# EntradaSensores.net
KiCad netlist of a schematic drawn in Altium Designer
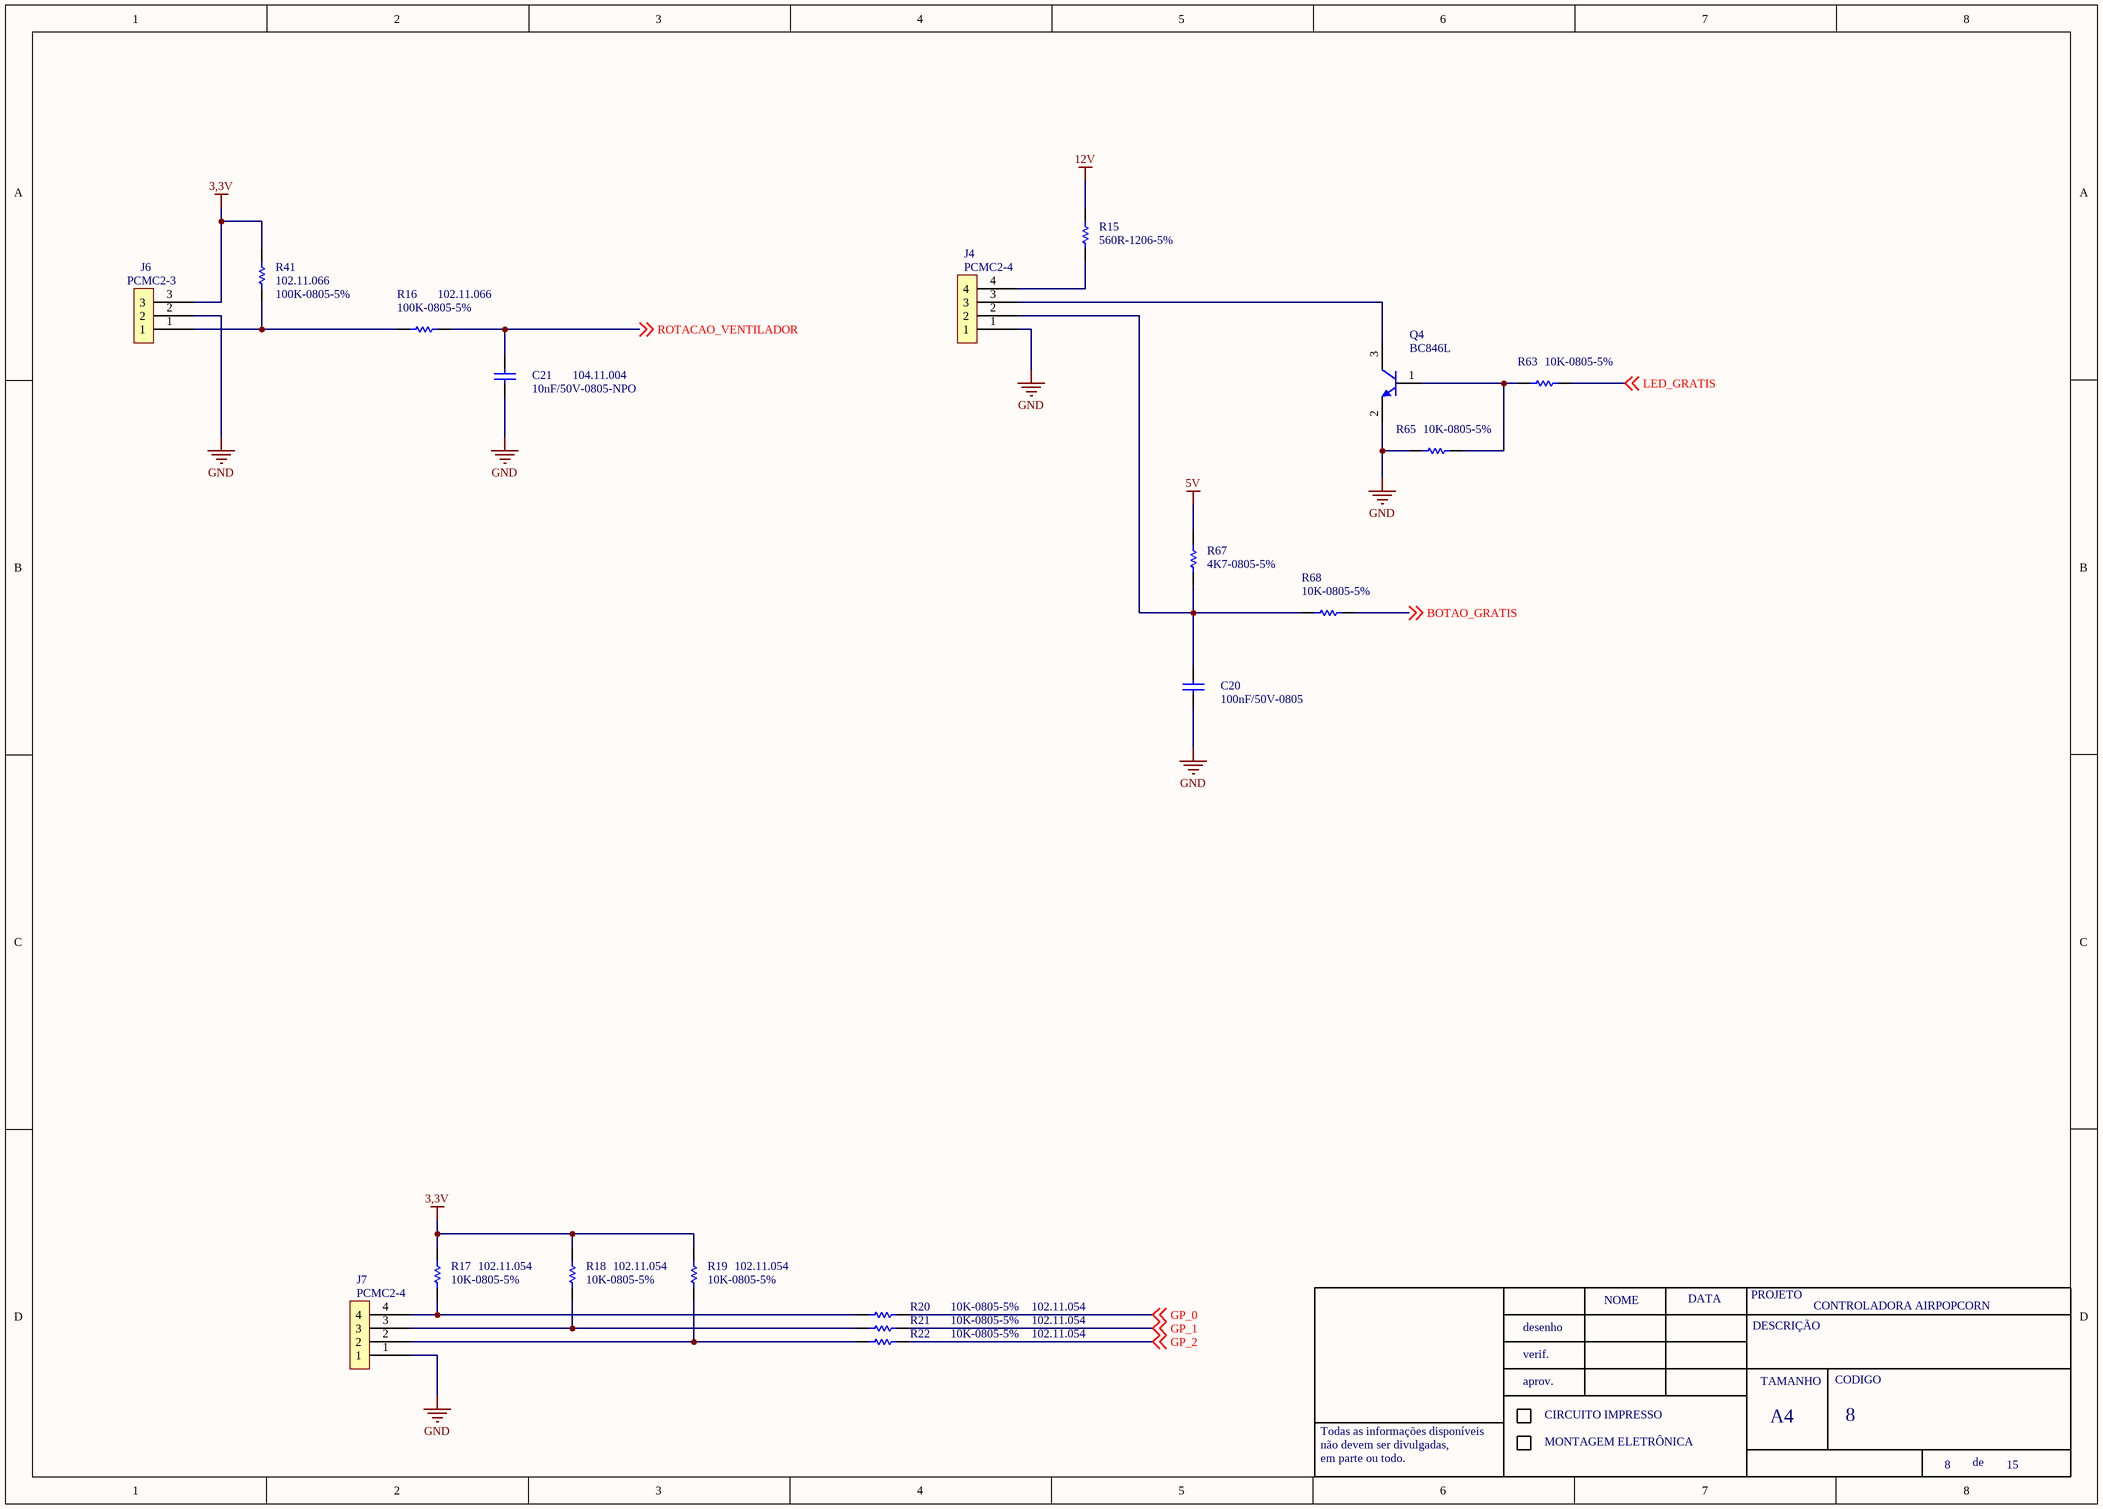
[diagram p0: EntradaSensores.SchDoc]

(export (version "E")
  (design (tool "Eeschema 10.0.6"))
  (components
    (comp (ref "C20")
      (value "100nF/50V-0805")
      (description "100nF/50-0805-NPO")
      (libsource (lib "AquinoLib") (part "100nF/50-0805-NPO"))
    )
    (comp (ref "C21")
      (value "10nF/50V-0805-NPO")
      (footprint "0805-REVISADO ONDA")
      (fields (field (name "ERP") "104.11.004"))
      (libsource (lib "AquinoLib") (part "10nF/50V-0805-NPO"))
    )
    (comp (ref "J4") (value "PCMC2-4") (footprint "PCMC2-4") (libsource (lib "AquinoLib") (part "PCMC2-4")))
    (comp (ref "J6") (value "PCMC2-3") (footprint "PCMC2-3") (libsource (lib "AquinoLib") (part "PCMC2-3")))
    (comp (ref "J7") (value "PCMC2-4") (footprint "PCMC2-4") (libsource (lib "AquinoLib") (part "PCMC2-4")))
    (comp (ref "Q4") (value "BC846L") (libsource (lib "AquinoLib") (part "BC846")))
    (comp (ref "R15")
      (value "560R-1206-5%")
      (description "1K2-0805-1%")
      (libsource (lib "AquinoLib") (part "1K2-0805-1%"))
    )
    (comp (ref "R16")
      (value "100K-0805-5%")
      (footprint "0805-REVISADO ONDA")
      (fields (field (name "ERP") "102.11.066"))
      (libsource (lib "AquinoLib") (part "100K-0805-5%"))
    )
    (comp (ref "R17")
      (value "10K-0805-5%")
      (footprint "0805-REVISADO ONDA")
      (fields (field (name "ERP") "102.11.054"))
      (libsource (lib "AquinoLib") (part "10K-0805-5%"))
    )
    (comp (ref "R18")
      (value "10K-0805-5%")
      (footprint "0805-REVISADO ONDA")
      (fields (field (name "ERP") "102.11.054"))
      (libsource (lib "AquinoLib") (part "10K-0805-5%"))
    )
    (comp (ref "R19")
      (value "10K-0805-5%")
      (footprint "0805-REVISADO ONDA")
      (fields (field (name "ERP") "102.11.054"))
      (libsource (lib "AquinoLib") (part "10K-0805-5%"))
    )
    (comp (ref "R20")
      (value "10K-0805-5%")
      (footprint "0805-REVISADO ONDA")
      (fields (field (name "ERP") "102.11.054"))
      (libsource (lib "AquinoLib") (part "10K-0805-5%"))
    )
    (comp (ref "R21")
      (value "10K-0805-5%")
      (footprint "0805-REVISADO ONDA")
      (fields (field (name "ERP") "102.11.054"))
      (libsource (lib "AquinoLib") (part "10K-0805-5%"))
    )
    (comp (ref "R22")
      (value "10K-0805-5%")
      (footprint "0805-REVISADO ONDA")
      (fields (field (name "ERP") "102.11.054"))
      (libsource (lib "AquinoLib") (part "10K-0805-5%"))
    )
    (comp (ref "R41")
      (value "100K-0805-5%")
      (footprint "0805-REVISADO ONDA")
      (fields (field (name "ERP") "102.11.066"))
      (libsource (lib "AquinoLib") (part "100K-0805-5%"))
    )
    (comp (ref "R63") (value "10K-0805-5%") (libsource (lib "AquinoLib") (part "10K-0805-5%")))
    (comp (ref "R65") (value "10K-0805-5%") (libsource (lib "AquinoLib") (part "10K-0805-5%")))
    (comp (ref "R67")
      (value "4K7-0805-5%")
      (description "4K7-1206-5%")
      (libsource (lib "AquinoLib") (part "4K7-1206-5%"))
    )
    (comp (ref "R68") (value "10K-0805-5%") (libsource (lib "AquinoLib") (part "10K-0805-5%")))
  )
  (nets
    (net (code "1") (name "3,3V") (class "Default")
      (node (ref "J6") (pin "3") (pinfunction "3_3") (pintype "passive"))
      (node (ref "R17") (pin "2") (pinfunction "2_2") (pintype "passive"))
      (node (ref "R18") (pin "2") (pinfunction "2_2") (pintype "passive"))
      (node (ref "R19") (pin "2") (pinfunction "2_2") (pintype "passive"))
      (node (ref "R41") (pin "2") (pinfunction "2_2") (pintype "passive"))
    )
    (net (code "2") (name "5V") (class "Default")
      (node (ref "R67") (pin "2") (pinfunction "2_2") (pintype "passive"))
    )
    (net (code "3") (name "12V") (class "Default")
      (node (ref "R15") (pin "1") (pinfunction "1_1") (pintype "passive"))
    )
    (net (code "4") (name "BOTAO_GRATIS") (class "Default")
      (node (ref "R68") (pin "1") (pinfunction "1_1") (pintype "passive"))
    )
    (net (code "5") (name "GND") (class "Default")
      (node (ref "C20") (pin "1") (pinfunction "1_1") (pintype "passive"))
      (node (ref "C21") (pin "1") (pinfunction "1_1") (pintype "passive"))
      (node (ref "J4") (pin "1") (pinfunction "1_1") (pintype "passive"))
      (node (ref "J6") (pin "2") (pinfunction "2_2") (pintype "passive"))
      (node (ref "J7") (pin "1") (pinfunction "1_1") (pintype "passive"))
      (node (ref "Q4") (pin "2") (pinfunction "E_2") (pintype "passive"))
      (node (ref "R65") (pin "1") (pinfunction "1_1") (pintype "passive"))
    )
    (net (code "6") (name "GP_0") (class "Default")
      (node (ref "R20") (pin "2") (pinfunction "2_2") (pintype "passive"))
    )
    (net (code "7") (name "GP_1") (class "Default")
      (node (ref "R21") (pin "2") (pinfunction "2_2") (pintype "passive"))
    )
    (net (code "8") (name "GP_2") (class "Default")
      (node (ref "R22") (pin "2") (pinfunction "2_2") (pintype "passive"))
    )
    (net (code "9") (name "LED_GRATIS") (class "Default")
      (node (ref "R63") (pin "2") (pinfunction "2_2") (pintype "passive"))
    )
    (net (code "10") (name "Net-(C20-Pad2)") (class "Default")
      (node (ref "C20") (pin "2") (pinfunction "2_2") (pintype "passive"))
      (node (ref "J4") (pin "2") (pinfunction "2_2") (pintype "passive"))
      (node (ref "R67") (pin "1") (pinfunction "1_1") (pintype "passive"))
      (node (ref "R68") (pin "2") (pinfunction "2_2") (pintype "passive"))
    )
    (net (code "11") (name "Net-(J4-Pad4)") (class "Default")
      (node (ref "J4") (pin "4") (pinfunction "4_4") (pintype "passive"))
      (node (ref "R15") (pin "2") (pinfunction "2_2") (pintype "passive"))
    )
    (net (code "12") (name "Net-(J6-Pad1)") (class "Default")
      (node (ref "J6") (pin "1") (pinfunction "1_1") (pintype "passive"))
      (node (ref "R16") (pin "1") (pinfunction "1_1") (pintype "passive"))
      (node (ref "R41") (pin "1") (pinfunction "1_1") (pintype "passive"))
    )
    (net (code "13") (name "Net-(J7-Pad2)") (class "Default")
      (node (ref "J7") (pin "2") (pinfunction "2_2") (pintype "passive"))
      (node (ref "R19") (pin "1") (pinfunction "1_1") (pintype "passive"))
      (node (ref "R22") (pin "1") (pinfunction "1_1") (pintype "passive"))
    )
    (net (code "14") (name "Net-(J7-Pad3)") (class "Default")
      (node (ref "J7") (pin "3") (pinfunction "3_3") (pintype "passive"))
      (node (ref "R18") (pin "1") (pinfunction "1_1") (pintype "passive"))
      (node (ref "R21") (pin "1") (pinfunction "1_1") (pintype "passive"))
    )
    (net (code "15") (name "Net-(J7-Pad4)") (class "Default")
      (node (ref "J7") (pin "4") (pinfunction "4_4") (pintype "passive"))
      (node (ref "R17") (pin "1") (pinfunction "1_1") (pintype "passive"))
      (node (ref "R20") (pin "1") (pinfunction "1_1") (pintype "passive"))
    )
    (net (code "16") (name "Net-(Q4-B)") (class "Default")
      (node (ref "Q4") (pin "1") (pinfunction "B_1") (pintype "passive"))
      (node (ref "R63") (pin "1") (pinfunction "1_1") (pintype "passive"))
      (node (ref "R65") (pin "2") (pinfunction "2_2") (pintype "passive"))
    )
    (net (code "17") (name "Net-(Q4-C)") (class "Default")
      (node (ref "J4") (pin "3") (pinfunction "3_3") (pintype "passive"))
      (node (ref "Q4") (pin "3") (pinfunction "C_3") (pintype "passive"))
    )
    (net (code "18") (name "ROTACAO_VENTILADOR") (class "Default")
      (node (ref "C21") (pin "2") (pinfunction "2_2") (pintype "passive"))
      (node (ref "R16") (pin "2") (pinfunction "2_2") (pintype "passive"))
    )
  )
)
